# Ada.net
KiCad netlist of a schematic drawn in Altium Designer
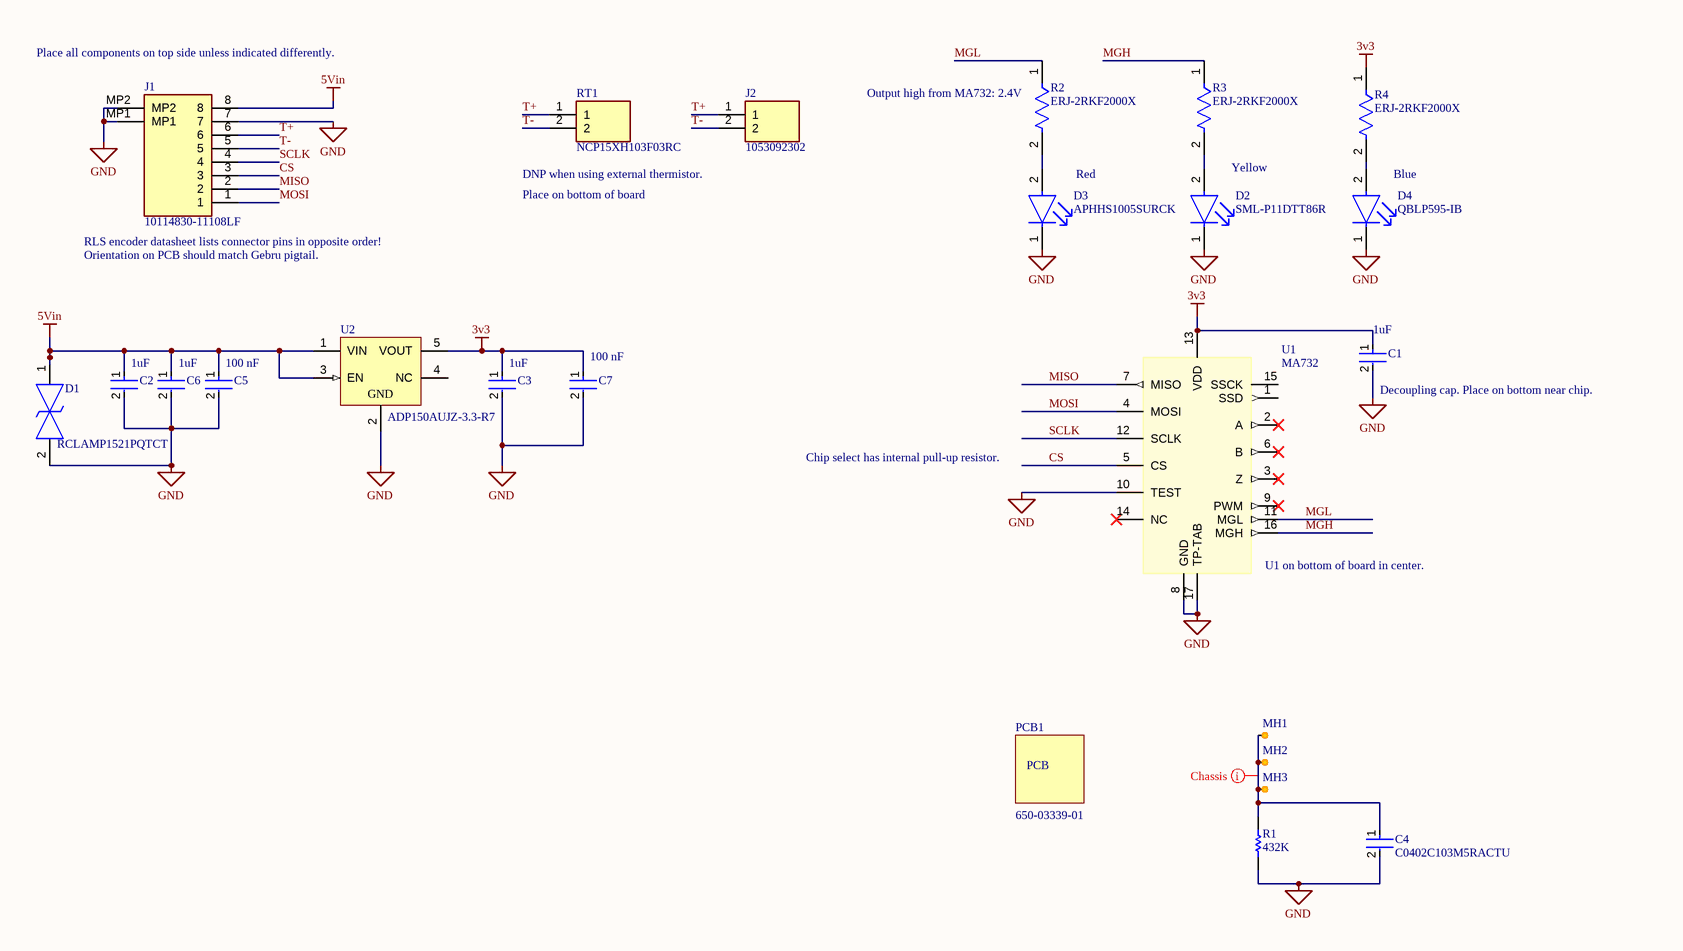
[diagram p0: Ada.SchDoc]

(export (version "E")
  (design (tool "Eeschema 10.0.6"))
  (components
    (comp (ref "C1")
      (value "CL03A105MQ3CSNC")
      (footprint "FP-CL03-IPC_A")
      (description "Cap Ceramic 1uF 6.3V X5R ±20% Pad SMD 0201 +85°C T/R")
      (fields (field (name "TOLERANCE") "20%") (field (name "CAPACITANCE") "1uF"))
      (libsource (lib "Altium Content Vault") (part "b4654b650e69147ec39a6b967a45e02"))
    )
    (comp (ref "C2")
      (value "CL03A105MQ3CSNC")
      (footprint "FP-CL03-IPC_A")
      (description "Cap Ceramic 1uF 6.3V X5R ±20% Pad SMD 0201 +85°C T/R")
      (fields (field (name "TOLERANCE") "20%") (field (name "CAPACITANCE") "1uF"))
      (libsource (lib "Altium Content Vault") (part "b4654b650e69147ec39a6b967a45e02"))
    )
    (comp (ref "C3")
      (value "CL03A105MQ3CSNC")
      (footprint "FP-CL03-IPC_A")
      (description "Cap Ceramic 1uF 6.3V X5R ±20% Pad SMD 0201 +85°C T/R")
      (fields (field (name "TOLERANCE") "20%") (field (name "CAPACITANCE") "1uF"))
      (libsource (lib "Altium Content Vault") (part "b4654b650e69147ec39a6b967a45e02"))
    )
    (comp (ref "C4")
      (value "C0402C103M5RACTU")
      (footprint "FP-C0402-BB-MFG")
      (description "CAP CER 10000PF 50V 20% X7R 0402")
      (fields
        (field (name "TOLERANCE") "0.2")
        (field (name "OCTOPART") "https://octopart.com/c0402c103m5ractu-kemet-17125571")
      )
      (libsource (lib "Altium Content Vault") (part "b4654b650e69147ec39a6b967a45e02"))
    )
    (comp (ref "C5")
      (value "100 nF")
      (footprint "FP-CC0402-MFG")
      (description "CAP CER 0.1UF 50V X5R 0402")
      (fields (field (name "TOLERANCE") "0.1") (field (name "MANUFACTURER") "YAGEO"))
      (libsource (lib "Altium Content Vault") (part "11868f565c42a9108669ba33697ecf6"))
    )
    (comp (ref "C6")
      (value "CL03A105MQ3CSNC")
      (footprint "FP-CL03-IPC_A")
      (description "Cap Ceramic 1uF 6.3V X5R ±20% Pad SMD 0201 +85°C T/R")
      (fields (field (name "TOLERANCE") "20%") (field (name "CAPACITANCE") "1uF"))
      (libsource (lib "Altium Content Vault") (part "b4654b650e69147ec39a6b967a45e02"))
    )
    (comp (ref "C7")
      (value "100 nF")
      (footprint "FP-CC0402-MFG")
      (description "CAP CER 0.1UF 50V X5R 0402")
      (fields (field (name "TOLERANCE") "0.1") (field (name "MANUFACTURER") "YAGEO"))
      (libsource (lib "Altium Content Vault") (part "11868f565c42a9108669ba33697ecf6"))
    )
    (comp (ref "D1")
      (value "RCLAMP1521PQTCT")
      (footprint "SamacSys:RCLAMP1521PQTCT")
      (description "TVS Diode (Bi-directional)")
      (fields (field (name "MOUSER PART NUMBER") "947-RCLAMP1521PQTCT"))
      (libsource (lib "*") (part "RCLAMP1521PQTCT"))
    )
    (comp (ref "D2")
      (value "SML-P11DTT86R")
      (footprint "FP-SML-P11-MFG")
      (description "LED ORANGE CLEAR 1006 SMD")
      (fields
        (field (name "OCTOPART") "https://octopart.com/sml-p11dtt86r-rohm-34112313")
        (field (name "MANUFACTURER") "Rohm")
      )
      (libsource (lib "Altium Content Vault") (part "8706943c75ba83719d021d2fdc84c58"))
    )
    (comp (ref "D3")
      (value "APHHS1005SURCK")
      (footprint "FP-APHHS1005SURCK-MFG")
      (description "LED RED CLEAR CHIP SMD")
      (libsource (lib "Altium Content Vault") (part "8706943c75ba83719d021d2fdc84c58"))
    )
    (comp (ref "D4")
      (value "QBLP595-IB")
      (footprint "FP-QBLP595-IB-MFG")
      (description "LED BLUE CLEAR 0402 SMD")
      (libsource (lib "Altium Content Vault") (part "8706943c75ba83719d021d2fdc84c58"))
    )
    (comp (ref "J1")
      (value "10114830-11108LF")
      (footprint "SamacSys:1011483011108LF")
      (description "Connector")
      (fields (field (name "MOUSER PART NUMBER") "649-10114830-11108LF"))
      (libsource (lib "SamacSys") (part "10114830-11108LF"))
    )
    (comp (ref "J2")
      (value "1053092302")
      (footprint "SamacSys:105309YY02_U")
      (description "Connector")
      (libsource (lib "SamacSys") (part "1053092302"))
    )
    (comp (ref "MH1")
      (value "MH")
      (footprint "MH_1.6MM")
      (description "MOUNTING HOLE, M1.6, 4.0mm PAD")
      (libsource (lib "AltiumReleaseLibDB") (part "MH"))
    )
    (comp (ref "MH2")
      (value "MH")
      (footprint "MH_1.6MM")
      (description "MOUNTING HOLE, M1.6, 4.0mm PAD")
      (libsource (lib "AltiumReleaseLibDB") (part "MH"))
    )
    (comp (ref "MH3")
      (value "MH")
      (footprint "MH_1.6MM")
      (description "MOUNTING HOLE, M1.6, 4.0mm PAD")
      (libsource (lib "AltiumReleaseLibDB") (part "MH"))
    )
    (comp (ref "PCB1")
      (value "651-PCB")
      (description "PCB")
      (libsource (lib "AltiumReleaseLibDB") (part "Label"))
    )
    (comp (ref "R1")
      (value "432K")
      (footprint "RESC1005X40X25NL05T10")
      (fields (field (name "PART NUMBER") "RC0402FR-07432KL") (field (name "MANUFACTURER") "Yageo"))
      (libsource (lib "Altium Content Vault") (part "RES"))
    )
    (comp (ref "R2")
      (value "ERJ-2RKF2000X")
      (footprint "FP-ERJ2RK-IPC_A")
      (description "RES SMD 200 OHM 1% 1/10W 0402")
      (fields (field (name "TOLERANCE") "1%"))
      (libsource (lib "Altium Content Vault") (part "1029c3af85768c4190bb7ad29bc67b5"))
    )
    (comp (ref "R3")
      (value "ERJ-2RKF2000X")
      (footprint "FP-ERJ2RK-IPC_A")
      (description "RES SMD 200 OHM 1% 1/10W 0402")
      (fields (field (name "TOLERANCE") "1%"))
      (libsource (lib "Altium Content Vault") (part "1029c3af85768c4190bb7ad29bc67b5"))
    )
    (comp (ref "R4")
      (value "ERJ-2RKF2000X")
      (footprint "FP-ERJ2RK-IPC_A")
      (description "RES SMD 200 OHM 1% 1/10W 0402")
      (fields (field (name "TOLERANCE") "1%"))
      (libsource (lib "Altium Content Vault") (part "1029c3af85768c4190bb7ad29bc67b5"))
    )
    (comp (ref "RT1")
      (value "NCP15XH103F03RC")
      (footprint "SamacSys:THRMC1005X55N")
      (description "Thermistor")
      (fields (field (name "MOUSER PART NUMBER") "81-NCP15XH103F03RC"))
      (libsource (lib "*") (part "NCP15XH103F03RC"))
    )
    (comp (ref "U1")
      (value "SENSOR_MPS_MA732")
      (footprint "QFN50P300X300X100-16-TP")
      (description "SENSOR, ANGLE, 9 BIT TO 14 BIT RESOLUTION, 14-BIT PWM OUTPUT, 3.3V, 12mA, QFN-16")
      (fields (field (name "MFG") "MPS") (field (name "MFG P/N") "MA732"))
      (libsource (lib "AltiumReleaseLibDB") (part "SENSOR_MPS_MA732"))
    )
    (comp (ref "U2")
      (value "ADP150AUJZ-3.3-R7")
      (footprint "ADI-UJ-5_M")
      (fields (field (name "MANUFACTURER") "Analog Devices"))
      (libsource (lib "Altium Content Vault") (part "ADI-ADP1XX-UJ-5"))
    )
  )
  (nets
    (net (code "1") (name "/CS") (class "Default")
      (node (ref "J1") (pin "3") (pinfunction "3_3") (pintype "passive"))
      (node (ref "U1") (pin "5") (pinfunction "CS_5") (pintype "passive"))
    )
    (net (code "2") (name "/MGH") (class "Default")
      (node (ref "R3") (pin "1") (pinfunction "1_1") (pintype "passive"))
      (node (ref "U1") (pin "16") (pinfunction "MGH_16") (pintype "output"))
    )
    (net (code "3") (name "/MGL") (class "Default")
      (node (ref "R2") (pin "1") (pinfunction "1_1") (pintype "passive"))
      (node (ref "U1") (pin "11") (pinfunction "MGL_11") (pintype "output"))
    )
    (net (code "4") (name "/MISO") (class "Default")
      (node (ref "J1") (pin "2") (pinfunction "2_2") (pintype "passive"))
      (node (ref "U1") (pin "7") (pinfunction "MISO_7") (pintype "output"))
    )
    (net (code "5") (name "/MOSI") (class "Default")
      (node (ref "J1") (pin "1") (pinfunction "1_1") (pintype "passive"))
      (node (ref "U1") (pin "4") (pinfunction "MOSI_4") (pintype "passive"))
    )
    (net (code "6") (name "/SCLK") (class "Default")
      (node (ref "J1") (pin "4") (pinfunction "4_4") (pintype "passive"))
      (node (ref "U1") (pin "12") (pinfunction "SCLK_12") (pintype "passive"))
    )
    (net (code "7") (name "/T+") (class "Default")
      (node (ref "J1") (pin "6") (pinfunction "6_6") (pintype "passive"))
      (node (ref "J2") (pin "1") (pinfunction "1_1") (pintype "passive"))
      (node (ref "RT1") (pin "1") (pinfunction "1_1") (pintype "passive"))
    )
    (net (code "8") (name "/T-") (class "Default")
      (node (ref "J1") (pin "5") (pinfunction "5_5") (pintype "passive"))
      (node (ref "J2") (pin "2") (pinfunction "2_2") (pintype "passive"))
      (node (ref "RT1") (pin "2") (pinfunction "2_2") (pintype "passive"))
    )
    (net (code "9") (name "3v3") (class "Default")
      (node (ref "C1") (pin "1") (pinfunction "1_1") (pintype "passive"))
      (node (ref "C3") (pin "1") (pinfunction "1_1") (pintype "passive"))
      (node (ref "C7") (pin "1") (pinfunction "1_1") (pintype "passive"))
      (node (ref "R4") (pin "1") (pinfunction "1_1") (pintype "passive"))
      (node (ref "U1") (pin "13") (pinfunction "VDD_13") (pintype "power_in"))
      (node (ref "U2") (pin "5") (pinfunction "VOUT_5") (pintype "power_in"))
    )
    (net (code "10") (name "5Vin") (class "Default")
      (node (ref "C2") (pin "1") (pinfunction "1_1") (pintype "passive"))
      (node (ref "C5") (pin "1") (pinfunction "1_1") (pintype "passive"))
      (node (ref "C6") (pin "1") (pinfunction "1_1") (pintype "passive"))
      (node (ref "D1") (pin "1") (pinfunction "1_1") (pintype "passive"))
      (node (ref "J1") (pin "8") (pinfunction "8_8") (pintype "passive"))
      (node (ref "U2") (pin "1") (pinfunction "VIN_1") (pintype "power_in"))
      (node (ref "U2") (pin "3") (pinfunction "EN_3") (pintype "input"))
    )
    (net (code "11") (name "GND") (class "Default")
      (node (ref "C1") (pin "2") (pinfunction "2_2") (pintype "passive"))
      (node (ref "C2") (pin "2") (pinfunction "2_2") (pintype "passive"))
      (node (ref "C3") (pin "2") (pinfunction "2_2") (pintype "passive"))
      (node (ref "C4") (pin "2") (pinfunction "2_2") (pintype "passive"))
      (node (ref "C5") (pin "2") (pinfunction "2_2") (pintype "passive"))
      (node (ref "C6") (pin "2") (pinfunction "2_2") (pintype "passive"))
      (node (ref "C7") (pin "2") (pinfunction "2_2") (pintype "passive"))
      (node (ref "D1") (pin "2") (pinfunction "2_2") (pintype "passive"))
      (node (ref "D2") (pin "1") (pinfunction "C_1") (pintype "passive"))
      (node (ref "D3") (pin "1") (pinfunction "C_1") (pintype "passive"))
      (node (ref "D4") (pin "1") (pinfunction "C_1") (pintype "passive"))
      (node (ref "J1") (pin "7") (pinfunction "7_7") (pintype "passive"))
      (node (ref "J1") (pin "MP1") (pinfunction "MP1_MP1") (pintype "passive"))
      (node (ref "J1") (pin "MP2") (pinfunction "MP2_MP2") (pintype "passive"))
      (node (ref "R1") (pin "1") (pinfunction "1_1") (pintype "passive"))
      (node (ref "U1") (pin "10") (pinfunction "TEST_10") (pintype "passive"))
      (node (ref "U1") (pin "17") (pinfunction "TP-TAB_17") (pintype "passive"))
      (node (ref "U1") (pin "8") (pinfunction "GND_8") (pintype "power_in"))
      (node (ref "U2") (pin "2") (pinfunction "GND_2") (pintype "power_in"))
    )
    (net (code "12") (name "Net-(C4-Pad1)") (class "Default")
      (node (ref "C4") (pin "1") (pinfunction "1_1") (pintype "passive"))
      (node (ref "MH1") (pin "1") (pintype "passive"))
      (node (ref "MH2") (pin "1") (pintype "passive"))
      (node (ref "MH3") (pin "1") (pintype "passive"))
      (node (ref "R1") (pin "2") (pinfunction "2_2") (pintype "passive"))
    )
    (net (code "13") (name "Net-(D2-A)") (class "Default")
      (node (ref "D2") (pin "2") (pinfunction "A_2") (pintype "passive"))
      (node (ref "R3") (pin "2") (pinfunction "2_2") (pintype "passive"))
    )
    (net (code "14") (name "Net-(D3-A)") (class "Default")
      (node (ref "D3") (pin "2") (pinfunction "A_2") (pintype "passive"))
      (node (ref "R2") (pin "2") (pinfunction "2_2") (pintype "passive"))
    )
    (net (code "15") (name "Net-(D4-A)") (class "Default")
      (node (ref "D4") (pin "2") (pinfunction "A_2") (pintype "passive"))
      (node (ref "R4") (pin "2") (pinfunction "2_2") (pintype "passive"))
    )
    (net (code "16") (name "unconnected-(U1-A-Pad2)") (class "Default")
      (node (ref "U1") (pin "2") (pinfunction "A_2") (pintype "output+no_connect"))
    )
    (net (code "17") (name "unconnected-(U1-B-Pad6)") (class "Default")
      (node (ref "U1") (pin "6") (pinfunction "B_6") (pintype "output+no_connect"))
    )
    (net (code "18") (name "unconnected-(U1-NC-Pad14)") (class "Default")
      (node (ref "U1") (pin "14") (pinfunction "NC_14") (pintype "passive+no_connect"))
    )
    (net (code "19") (name "unconnected-(U1-PWM-Pad9)") (class "Default")
      (node (ref "U1") (pin "9") (pinfunction "PWM_9") (pintype "output+no_connect"))
    )
    (net (code "20") (name "unconnected-(U1-SSCK-Pad15)") (class "Default")
      (node (ref "U1") (pin "15") (pinfunction "SSCK_15") (pintype "passive"))
    )
    (net (code "21") (name "unconnected-(U1-SSD-Pad1)") (class "Default")
      (node (ref "U1") (pin "1") (pinfunction "SSD_1") (pintype "output"))
    )
    (net (code "22") (name "unconnected-(U1-Z-Pad3)") (class "Default")
      (node (ref "U1") (pin "3") (pinfunction "Z_3") (pintype "output+no_connect"))
    )
    (net (code "23") (name "unconnected-(U2-NC-Pad4)") (class "Default")
      (node (ref "U2") (pin "4") (pinfunction "NC_4") (pintype "passive"))
    )
  )
)
